# Pico_Audio_v0_13.net
KiCad netlist of a schematic drawn in EAGLE
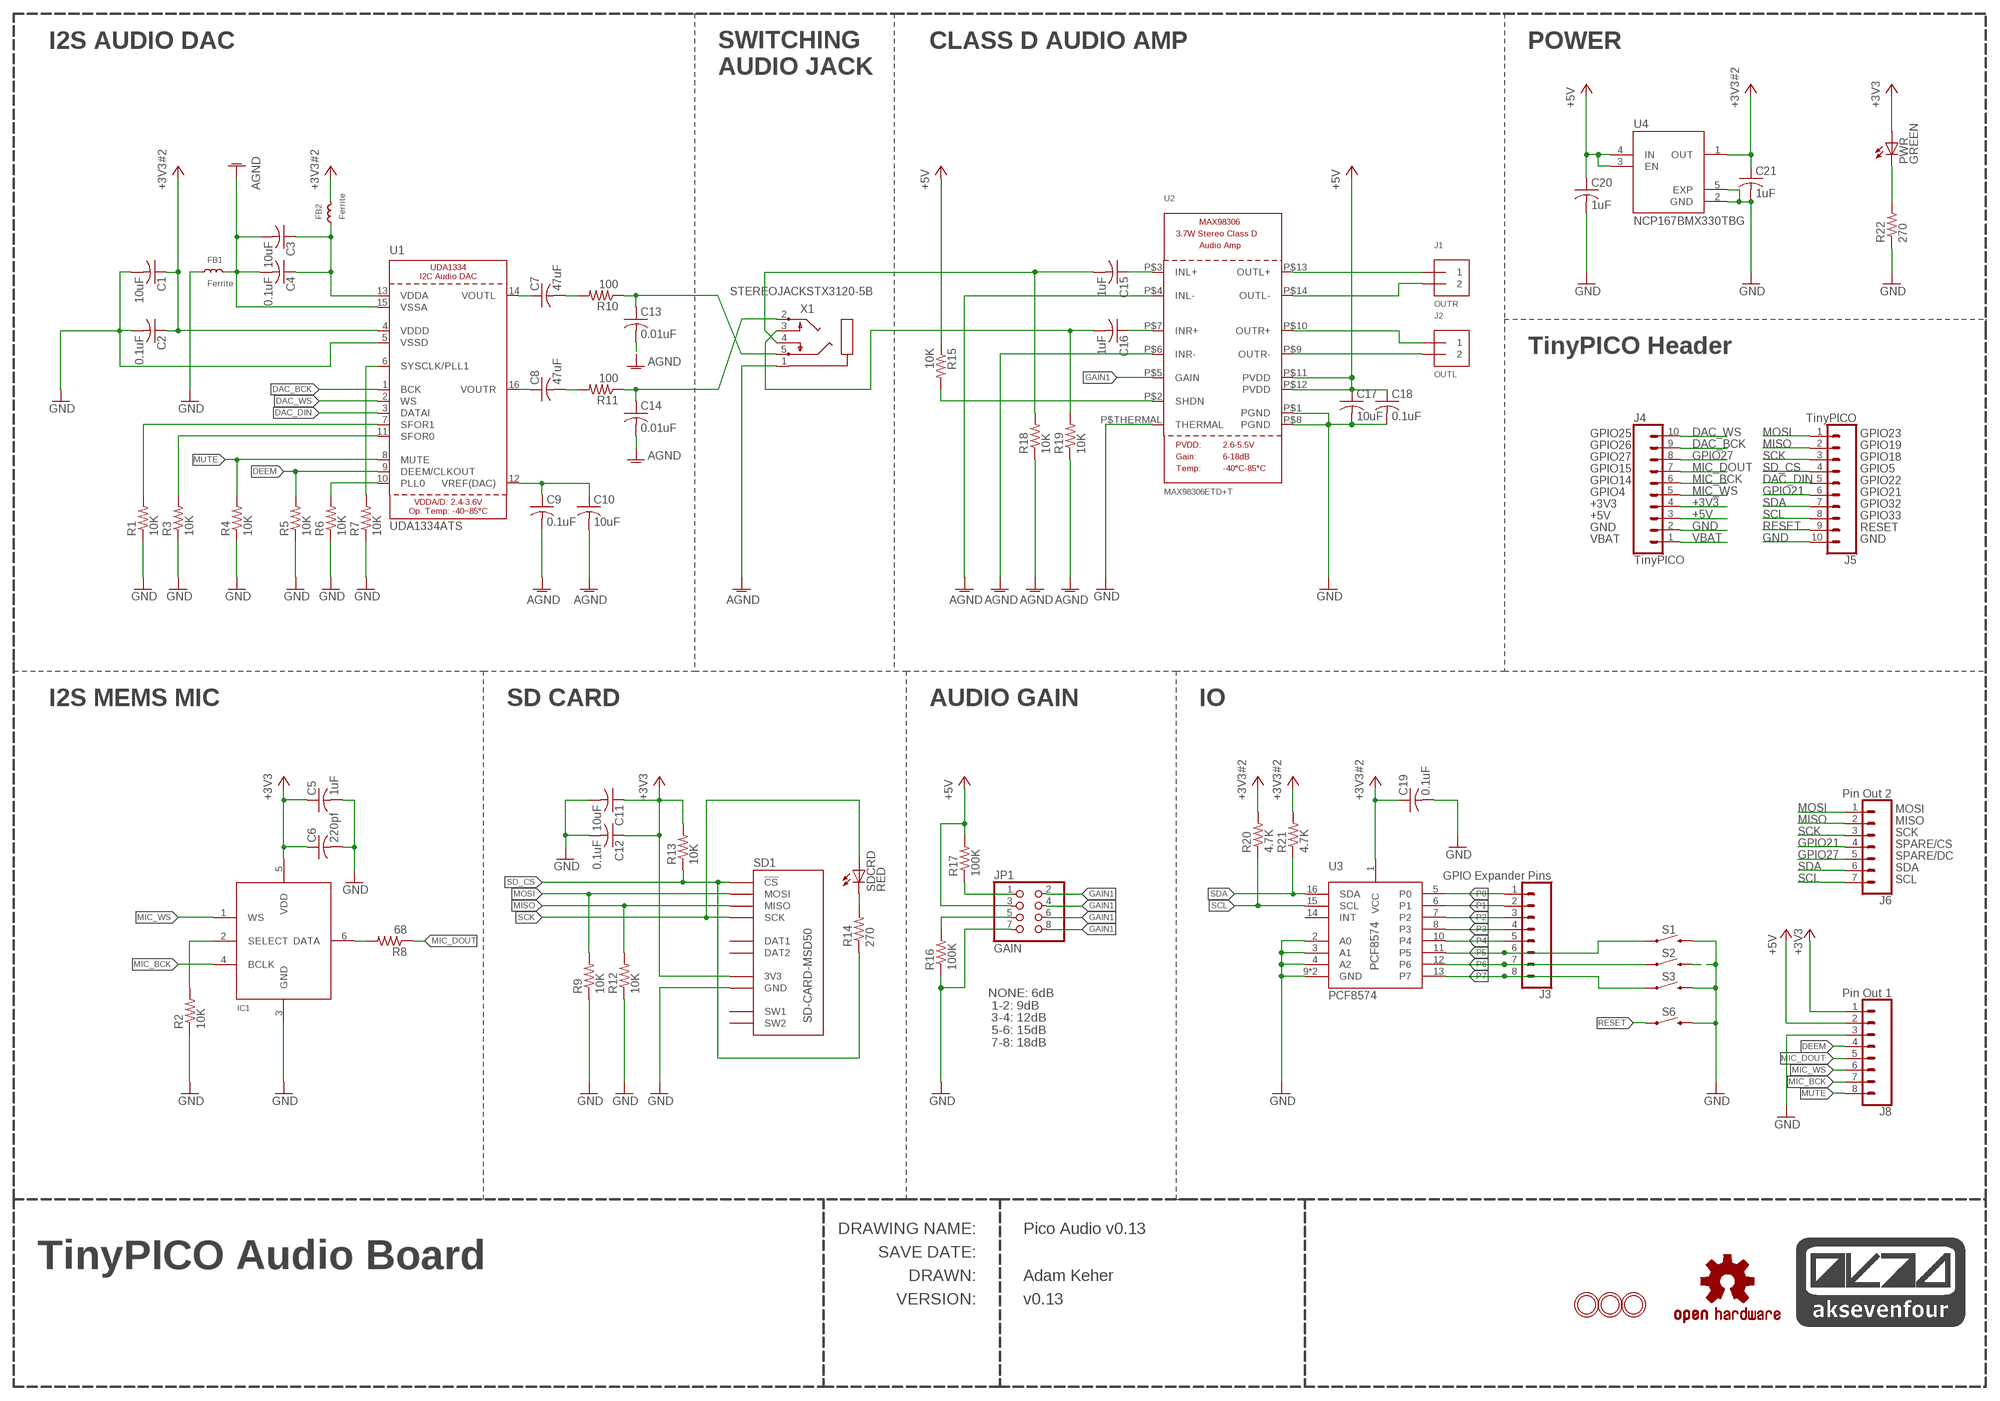
[diagram p0: schematic, sheet 1]

(export (version "E")
  (design (tool "Eeschema 10.0.6"))
  (components
    (comp (ref "AK74LOGO2")
      (value "AK74_LOGOAK74_LOGO_SMALL")
      (footprint "eagle-import:AK74_LOGO_MEDIUM")
      (libsource (lib "eagle-import") (part "AK74_LOGOAK74_LOGO_SMALL"))
    )
    (comp (ref "C1")
      (value "10uF")
      (footprint "eagle-import:C0603K")
      (libsource (lib "eagle-import") (part "C-USC0603K"))
    )
    (comp (ref "C2")
      (value "0.1uF")
      (footprint "eagle-import:C0402K")
      (libsource (lib "eagle-import") (part "C-USC0402K"))
    )
    (comp (ref "C3")
      (value "10uF")
      (footprint "eagle-import:C0603K")
      (libsource (lib "eagle-import") (part "C-USC0603K"))
    )
    (comp (ref "C4")
      (value "0.1uF")
      (footprint "eagle-import:C0402K")
      (libsource (lib "eagle-import") (part "C-USC0402K"))
    )
    (comp (ref "C5")
      (value "1uF")
      (footprint "eagle-import:C0402K")
      (libsource (lib "eagle-import") (part "C-USC0402K"))
    )
    (comp (ref "C6")
      (value "220pf")
      (footprint "eagle-import:C0402K")
      (libsource (lib "eagle-import") (part "C-USC0402K"))
    )
    (comp (ref "C7")
      (value "47uF")
      (footprint "eagle-import:C1210K")
      (libsource (lib "eagle-import") (part "C-USC1210K"))
    )
    (comp (ref "C8")
      (value "47uF")
      (footprint "eagle-import:C1210K")
      (libsource (lib "eagle-import") (part "C-USC1210K"))
    )
    (comp (ref "C9")
      (value "0.1uF")
      (footprint "eagle-import:C0402K")
      (libsource (lib "eagle-import") (part "C-USC0402K"))
    )
    (comp (ref "C10")
      (value "10uF")
      (footprint "eagle-import:C0603K")
      (libsource (lib "eagle-import") (part "C-USC0603K"))
    )
    (comp (ref "C11")
      (value "10uF")
      (footprint "eagle-import:C0603K")
      (libsource (lib "eagle-import") (part "C-USC0603K"))
    )
    (comp (ref "C12")
      (value "0.1uF")
      (footprint "eagle-import:C0402K")
      (libsource (lib "eagle-import") (part "C-USC0402K"))
    )
    (comp (ref "C13")
      (value "0.01uF")
      (footprint "eagle-import:C0402K")
      (libsource (lib "eagle-import") (part "C-USC0402K"))
    )
    (comp (ref "C14")
      (value "0.01uF")
      (footprint "eagle-import:C0402K")
      (libsource (lib "eagle-import") (part "C-USC0402K"))
    )
    (comp (ref "C15")
      (value "1uF")
      (footprint "eagle-import:C0402K")
      (libsource (lib "eagle-import") (part "C-USC0402K"))
    )
    (comp (ref "C16")
      (value "1uF")
      (footprint "eagle-import:C0402K")
      (libsource (lib "eagle-import") (part "C-USC0402K"))
    )
    (comp (ref "C17")
      (value "10uF")
      (footprint "eagle-import:C0603K")
      (libsource (lib "eagle-import") (part "C-USC0603K"))
    )
    (comp (ref "C18")
      (value "0.1uF")
      (footprint "eagle-import:C0402K")
      (libsource (lib "eagle-import") (part "C-USC0402K"))
    )
    (comp (ref "C19")
      (value "0.1uF")
      (footprint "eagle-import:C0402K")
      (libsource (lib "eagle-import") (part "C-USC0402K"))
    )
    (comp (ref "C20")
      (value "1uF")
      (footprint "eagle-import:C0402K")
      (libsource (lib "eagle-import") (part "C-USC0402K"))
    )
    (comp (ref "C21")
      (value "1uF")
      (footprint "eagle-import:C0402K")
      (libsource (lib "eagle-import") (part "C-USC0402K"))
    )
    (comp (ref "FB1")
      (value "Ferrite")
      (footprint "eagle-import:R0805")
      (libsource (lib "eagle-import") (part "FERRITEL0805"))
    )
    (comp (ref "FB2")
      (value "Ferrite")
      (footprint "eagle-import:R0805")
      (libsource (lib "eagle-import") (part "FERRITEL0805"))
    )
    (comp (ref "IC1")
      (value "MIC_I2S_SPH0645")
      (footprint "eagle-import:SPH0645LM4H")
      (libsource (lib "eagle-import") (part "MIC_I2S_SPH0645"))
    )
    (comp (ref "J1")
      (value "OUTR")
      (footprint "eagle-import:TERMBLOCK_1X2-3.5MM")
      (libsource (lib "eagle-import") (part "TERMBLOCK_1X2"))
    )
    (comp (ref "J2")
      (value "OUTL")
      (footprint "eagle-import:TERMBLOCK_1X2-3.5MM")
      (libsource (lib "eagle-import") (part "TERMBLOCK_1X2"))
    )
    (comp (ref "J3")
      (value "GPIO Expander Pins")
      (footprint "eagle-import:1X08_NO_SILK")
      (libsource (lib "eagle-import") (part "CONN_08NO_SILK_FEMALE_PTH"))
    )
    (comp (ref "J4")
      (value "TinyPICO")
      (footprint "eagle-import:1X10_NO_SILK")
      (libsource (lib "eagle-import") (part "TINYPICO_HEADER_10NO_SILK_PTH_FEMALE"))
    )
    (comp (ref "J5")
      (value "TinyPICO")
      (footprint "eagle-import:1X10_NO_SILK")
      (libsource (lib "eagle-import") (part "TINYPICO_HEADER_10NO_SILK_PTH_FEMALE"))
    )
    (comp (ref "J6")
      (value "Pin Out 2")
      (footprint "eagle-import:1X07_NO_SILK")
      (libsource (lib "eagle-import") (part "CONN_07NO_SILK"))
    )
    (comp (ref "J8")
      (value "Pin Out 1")
      (footprint "eagle-import:1X08_NO_SILK")
      (libsource (lib "eagle-import") (part "CONN_08NO_SILK_FEMALE_PTH"))
    )
    (comp (ref "JP1")
      (value "GAIN")
      (footprint "eagle-import:2X04")
      (libsource (lib "eagle-import") (part "PINHD-2X4"))
    )
    (comp (ref "LOGO1")
      (value "OSHW-LOGOM")
      (footprint "eagle-import:OSHW-LOGO-M")
      (libsource (lib "eagle-import") (part "OSHW-LOGOM"))
    )
    (comp (ref "MH1")
      (value "MOUNTINGHOLE2.5")
      (footprint "eagle-import:MOUNTINGHOLE_2.5_PLATED")
      (libsource (lib "eagle-import") (part "MOUNTINGHOLE2.5"))
    )
    (comp (ref "MH2")
      (value "MOUNTINGHOLE2.5")
      (footprint "eagle-import:MOUNTINGHOLE_2.5_PLATED")
      (libsource (lib "eagle-import") (part "MOUNTINGHOLE2.5"))
    )
    (comp (ref "MH3")
      (value "MOUNTINGHOLE2.5")
      (footprint "eagle-import:MOUNTINGHOLE_2.5_PLATED")
      (libsource (lib "eagle-import") (part "MOUNTINGHOLE2.5"))
    )
    (comp (ref "PWR")
      (value "GREEN")
      (footprint "eagle-import:CHIP-LED0805")
      (libsource (lib "eagle-import") (part "LEDCHIP-LED0805"))
    )
    (comp (ref "R1")
      (value "10K")
      (footprint "eagle-import:R0402")
      (libsource (lib "eagle-import") (part "R-US_R0402"))
    )
    (comp (ref "R2")
      (value "10K")
      (footprint "eagle-import:R0402")
      (libsource (lib "eagle-import") (part "R-US_R0402"))
    )
    (comp (ref "R3")
      (value "10K")
      (footprint "eagle-import:R0402")
      (libsource (lib "eagle-import") (part "R-US_R0402"))
    )
    (comp (ref "R4")
      (value "10K")
      (footprint "eagle-import:R0402")
      (libsource (lib "eagle-import") (part "R-US_R0402"))
    )
    (comp (ref "R5")
      (value "10K")
      (footprint "eagle-import:R0402")
      (libsource (lib "eagle-import") (part "R-US_R0402"))
    )
    (comp (ref "R6")
      (value "10K")
      (footprint "eagle-import:R0402")
      (libsource (lib "eagle-import") (part "R-US_R0402"))
    )
    (comp (ref "R7")
      (value "10K")
      (footprint "eagle-import:R0402")
      (libsource (lib "eagle-import") (part "R-US_R0402"))
    )
    (comp (ref "R8")
      (value "68")
      (footprint "eagle-import:R0402")
      (libsource (lib "eagle-import") (part "R-US_R0402"))
    )
    (comp (ref "R9")
      (value "10K")
      (footprint "eagle-import:R0402")
      (libsource (lib "eagle-import") (part "R-US_R0402"))
    )
    (comp (ref "R10")
      (value "100")
      (footprint "eagle-import:R0402")
      (libsource (lib "eagle-import") (part "R-US_R0402"))
    )
    (comp (ref "R11")
      (value "100")
      (footprint "eagle-import:R0402")
      (libsource (lib "eagle-import") (part "R-US_R0402"))
    )
    (comp (ref "R12")
      (value "10K")
      (footprint "eagle-import:R0402")
      (libsource (lib "eagle-import") (part "R-US_R0402"))
    )
    (comp (ref "R13")
      (value "10K")
      (footprint "eagle-import:R0402")
      (libsource (lib "eagle-import") (part "R-US_R0402"))
    )
    (comp (ref "R14")
      (value "270")
      (footprint "eagle-import:R0402")
      (libsource (lib "eagle-import") (part "R-US_R0402"))
    )
    (comp (ref "R15")
      (value "10K")
      (footprint "eagle-import:R0402")
      (libsource (lib "eagle-import") (part "R-US_R0402"))
    )
    (comp (ref "R16")
      (value "100K")
      (footprint "eagle-import:R0402")
      (libsource (lib "eagle-import") (part "R-US_R0402"))
    )
    (comp (ref "R17")
      (value "100K")
      (footprint "eagle-import:R0402")
      (libsource (lib "eagle-import") (part "R-US_R0402"))
    )
    (comp (ref "R18")
      (value "10K")
      (footprint "eagle-import:R0402")
      (libsource (lib "eagle-import") (part "R-US_R0402"))
    )
    (comp (ref "R19")
      (value "10K")
      (footprint "eagle-import:R0402")
      (libsource (lib "eagle-import") (part "R-US_R0402"))
    )
    (comp (ref "R20")
      (value "4.7K")
      (footprint "eagle-import:R0402")
      (libsource (lib "eagle-import") (part "R-US_R0402"))
    )
    (comp (ref "R21")
      (value "4.7K")
      (footprint "eagle-import:R0402")
      (libsource (lib "eagle-import") (part "R-US_R0402"))
    )
    (comp (ref "R22")
      (value "270")
      (footprint "eagle-import:R0402")
      (libsource (lib "eagle-import") (part "R-US_R0402"))
    )
    (comp (ref "S1")
      (value "MOMENTARY-SWITCH-SPST-SMD-4.6X2.8MM")
      (footprint "eagle-import:TACTILE_SWITCH_SMD_4.6X2.8MM")
      (libsource (lib "eagle-import") (part "MOMENTARY-SWITCH-SPST-SMD-4.6X2.8MM"))
    )
    (comp (ref "S2")
      (value "MOMENTARY-SWITCH-SPST-SMD-4.6X2.8MM")
      (footprint "eagle-import:TACTILE_SWITCH_SMD_4.6X2.8MM")
      (libsource (lib "eagle-import") (part "MOMENTARY-SWITCH-SPST-SMD-4.6X2.8MM"))
    )
    (comp (ref "S3")
      (value "MOMENTARY-SWITCH-SPST-SMD-4.6X2.8MM")
      (footprint "eagle-import:TACTILE_SWITCH_SMD_4.6X2.8MM")
      (libsource (lib "eagle-import") (part "MOMENTARY-SWITCH-SPST-SMD-4.6X2.8MM"))
    )
    (comp (ref "S6")
      (value "MOMENTARY-SWITCH-SPST-SMD-4.6X2.8MM")
      (footprint "eagle-import:TACTILE_SWITCH_SMD_4.6X2.8MM")
      (libsource (lib "eagle-import") (part "MOMENTARY-SWITCH-SPST-SMD-4.6X2.8MM"))
    )
    (comp (ref "SD1")
      (value "SD-CARD-MSD50")
      (footprint "eagle-import:SD_5031821853")
      (libsource (lib "eagle-import") (part "SD-CARD-MSD50"))
    )
    (comp (ref "SDCRD")
      (value "RED")
      (footprint "eagle-import:CHIP-LED0805")
      (libsource (lib "eagle-import") (part "LEDCHIP-LED0805"))
    )
    (comp (ref "U1")
      (value "UDA1334ATS")
      (footprint "eagle-import:SSOP16_4.4MM")
      (libsource (lib "eagle-import") (part "AUDIO_I2S_UDA1334{dblquote}{dblquote}"))
    )
    (comp (ref "U2")
      (value "MAX98306ETD+T")
      (footprint "eagle-import:TDFN14_3X3MM")
      (libsource (lib "eagle-import") (part "AUDIOAMP_MAX98306"))
    )
    (comp (ref "U3")
      (value "PCF8574")
      (footprint "eagle-import:QFN-16-3MM")
      (libsource (lib "eagle-import") (part "PCF8574"))
    )
    (comp (ref "U4")
      (value "NCP170AMX300TCG")
      (footprint "eagle-import:VREG_NCP170AMX300TCG")
      (fields (field (name "MF") "ON Semiconductor"))
      (libsource (lib "eagle-import") (part "NCP170AMX300TCG"))
    )
    (comp (ref "X1")
      (value "STEREOJACKSTX3120-5B")
      (footprint "eagle-import:STX3100")
      (libsource (lib "eagle-import") (part "STEREOJACKSTX3120-5B"))
    )
  )
  (nets
    (net (code "1") (name "+3V3") (class "Default")
      (node (ref "C11") (pin "1") (pinfunction "1_1") (pintype "passive"))
      (node (ref "C12") (pin "1") (pinfunction "1_1") (pintype "passive"))
      (node (ref "C5") (pin "1") (pinfunction "1_1") (pintype "passive"))
      (node (ref "C6") (pin "1") (pinfunction "1_1") (pintype "passive"))
      (node (ref "IC1") (pin "5") (pinfunction "VDD_5") (pintype "power_in"))
      (node (ref "J4") (pin "4") (pinfunction "4_4") (pintype "passive"))
      (node (ref "J8") (pin "1") (pinfunction "1_1") (pintype "passive"))
      (node (ref "PWR") (pin "A") (pinfunction "A_A") (pintype "passive"))
      (node (ref "R13") (pin "2") (pinfunction "2_2") (pintype "passive"))
      (node (ref "SD1") (pin "VCC") (pinfunction "3V3_VCC") (pintype "bidirectional"))
    )
    (net (code "2") (name "+3V3#2") (class "Default")
      (node (ref "C1") (pin "1") (pinfunction "1_1") (pintype "passive"))
      (node (ref "C19") (pin "1") (pinfunction "1_1") (pintype "passive"))
      (node (ref "C2") (pin "1") (pinfunction "1_1") (pintype "passive"))
      (node (ref "C21") (pin "1") (pinfunction "1_1") (pintype "passive"))
      (node (ref "FB2") (pin "2") (pinfunction "2_2") (pintype "passive"))
      (node (ref "R20") (pin "2") (pinfunction "2_2") (pintype "passive"))
      (node (ref "R21") (pin "2") (pinfunction "2_2") (pintype "passive"))
      (node (ref "U1") (pin "4") (pinfunction "VDDD_4") (pintype "power_in"))
      (node (ref "U3") (pin "1") (pinfunction "VCC_1") (pintype "bidirectional"))
      (node (ref "U4") (pin "1") (pinfunction "OUT_1") (pintype "output"))
    )
    (net (code "3") (name "+5V") (class "Default")
      (node (ref "C17") (pin "1") (pinfunction "1_1") (pintype "passive"))
      (node (ref "C18") (pin "1") (pinfunction "1_1") (pintype "passive"))
      (node (ref "C20") (pin "1") (pinfunction "1_1") (pintype "passive"))
      (node (ref "J4") (pin "3") (pinfunction "3_3") (pintype "passive"))
      (node (ref "J8") (pin "2") (pinfunction "2_2") (pintype "passive"))
      (node (ref "JP1") (pin "3") (pinfunction "3_3") (pintype "passive"))
      (node (ref "R15") (pin "1") (pinfunction "1_1") (pintype "passive"))
      (node (ref "R17") (pin "2") (pinfunction "2_2") (pintype "passive"))
      (node (ref "U2") (pin "P$11") (pinfunction "PVDD_P$11") (pintype "power_in"))
      (node (ref "U2") (pin "P$12") (pinfunction "PVDD_P$12") (pintype "power_in"))
      (node (ref "U4") (pin "3") (pinfunction "EN_3") (pintype "input"))
      (node (ref "U4") (pin "4") (pinfunction "IN_4") (pintype "input"))
    )
    (net (code "4") (name "/GPIO21") (class "Default")
      (node (ref "J5") (pin "6") (pinfunction "6_6") (pintype "passive"))
      (node (ref "J6") (pin "4") (pinfunction "4_4") (pintype "passive"))
    )
    (net (code "5") (name "/GPIO27") (class "Default")
      (node (ref "J4") (pin "8") (pinfunction "8_8") (pintype "passive"))
      (node (ref "J6") (pin "5") (pinfunction "5_5") (pintype "passive"))
    )
    (net (code "6") (name "/VBAT") (class "Default")
      (node (ref "J4") (pin "1") (pinfunction "1_1") (pintype "passive"))
    )
    (net (code "7") (name "AGND") (class "Default")
      (node (ref "C10") (pin "2") (pinfunction "2_2") (pintype "passive"))
      (node (ref "C13") (pin "2") (pinfunction "2_2") (pintype "passive"))
      (node (ref "C14") (pin "2") (pinfunction "2_2") (pintype "passive"))
      (node (ref "C3") (pin "2") (pinfunction "2_2") (pintype "passive"))
      (node (ref "C4") (pin "2") (pinfunction "2_2") (pintype "passive"))
      (node (ref "C9") (pin "2") (pinfunction "2_2") (pintype "passive"))
      (node (ref "FB1") (pin "2") (pinfunction "2_2") (pintype "passive"))
      (node (ref "R18") (pin "1") (pinfunction "1_1") (pintype "passive"))
      (node (ref "R19") (pin "1") (pinfunction "1_1") (pintype "passive"))
      (node (ref "U1") (pin "15") (pinfunction "VSSA_15") (pintype "power_in"))
      (node (ref "U2") (pin "P$4") (pinfunction "INL-_P$4") (pintype "input"))
      (node (ref "U2") (pin "P$6") (pinfunction "INR-_P$6") (pintype "input"))
      (node (ref "X1") (pin "1") (pinfunction "1_1") (pintype "passive"))
    )
    (net (code "8") (name "DAC_BCK") (class "Default")
      (node (ref "J4") (pin "9") (pinfunction "9_9") (pintype "passive"))
      (node (ref "U1") (pin "1") (pinfunction "BCK_1") (pintype "input"))
    )
    (net (code "9") (name "DAC_DIN") (class "Default")
      (node (ref "J5") (pin "5") (pinfunction "5_5") (pintype "passive"))
      (node (ref "U1") (pin "3") (pinfunction "DATAI_3") (pintype "input"))
    )
    (net (code "10") (name "DAC_WS") (class "Default")
      (node (ref "J4") (pin "10") (pinfunction "10_10") (pintype "passive"))
      (node (ref "U1") (pin "2") (pinfunction "WS_2") (pintype "input"))
    )
    (net (code "11") (name "DEEM") (class "Default")
      (node (ref "J8") (pin "4") (pinfunction "4_4") (pintype "passive"))
      (node (ref "R5") (pin "2") (pinfunction "2_2") (pintype "passive"))
      (node (ref "U1") (pin "9") (pinfunction "DEEM/CLKOUT_9") (pintype "bidirectional"))
    )
    (net (code "12") (name "GAIN1") (class "Default")
      (node (ref "JP1") (pin "2") (pinfunction "2_2") (pintype "passive"))
      (node (ref "JP1") (pin "4") (pinfunction "4_4") (pintype "passive"))
      (node (ref "JP1") (pin "6") (pinfunction "6_6") (pintype "passive"))
      (node (ref "JP1") (pin "8") (pinfunction "8_8") (pintype "passive"))
      (node (ref "U2") (pin "P$5") (pinfunction "GAIN_P$5") (pintype "input"))
    )
    (net (code "13") (name "GND") (class "Default")
      (node (ref "C1") (pin "2") (pinfunction "2_2") (pintype "passive"))
      (node (ref "C11") (pin "2") (pinfunction "2_2") (pintype "passive"))
      (node (ref "C12") (pin "2") (pinfunction "2_2") (pintype "passive"))
      (node (ref "C17") (pin "2") (pinfunction "2_2") (pintype "passive"))
      (node (ref "C18") (pin "2") (pinfunction "2_2") (pintype "passive"))
      (node (ref "C19") (pin "2") (pinfunction "2_2") (pintype "passive"))
      (node (ref "C2") (pin "2") (pinfunction "2_2") (pintype "passive"))
      (node (ref "C20") (pin "2") (pinfunction "2_2") (pintype "passive"))
      (node (ref "C21") (pin "2") (pinfunction "2_2") (pintype "passive"))
      (node (ref "C5") (pin "2") (pinfunction "2_2") (pintype "passive"))
      (node (ref "C6") (pin "2") (pinfunction "2_2") (pintype "passive"))
      (node (ref "FB1") (pin "1") (pinfunction "1_1") (pintype "passive"))
      (node (ref "IC1") (pin "3") (pinfunction "GND_3") (pintype "power_in"))
      (node (ref "J4") (pin "2") (pinfunction "2_2") (pintype "passive"))
      (node (ref "J5") (pin "10") (pinfunction "10_10") (pintype "passive"))
      (node (ref "J8") (pin "3") (pinfunction "3_3") (pintype "passive"))
      (node (ref "JP1") (pin "7") (pinfunction "7_7") (pintype "passive"))
      (node (ref "R1") (pin "1") (pinfunction "1_1") (pintype "passive"))
      (node (ref "R12") (pin "1") (pinfunction "1_1") (pintype "passive"))
      (node (ref "R16") (pin "1") (pinfunction "1_1") (pintype "passive"))
      (node (ref "R2") (pin "1") (pinfunction "1_1") (pintype "passive"))
      (node (ref "R22") (pin "1") (pinfunction "1_1") (pintype "passive"))
      (node (ref "R3") (pin "1") (pinfunction "1_1") (pintype "passive"))
      (node (ref "R4") (pin "1") (pinfunction "1_1") (pintype "passive"))
      (node (ref "R5") (pin "1") (pinfunction "1_1") (pintype "passive"))
      (node (ref "R6") (pin "1") (pinfunction "1_1") (pintype "passive"))
      (node (ref "R7") (pin "1") (pinfunction "1_1") (pintype "passive"))
      (node (ref "R9") (pin "1") (pinfunction "1_1") (pintype "passive"))
      (node (ref "S1") (pin "3") (pinfunction "2_3") (pintype "passive"))
      (node (ref "S1") (pin "4") (pinfunction "2_4") (pintype "passive"))
      (node (ref "S2") (pin "3") (pinfunction "2_3") (pintype "passive"))
      (node (ref "S2") (pin "4") (pinfunction "2_4") (pintype "passive"))
      (node (ref "S3") (pin "3") (pinfunction "2_3") (pintype "passive"))
      (node (ref "S3") (pin "4") (pinfunction "2_4") (pintype "passive"))
      (node (ref "S6") (pin "3") (pinfunction "2_3") (pintype "passive"))
      (node (ref "S6") (pin "4") (pinfunction "2_4") (pintype "passive"))
      (node (ref "SD1") (pin "GND") (pinfunction "GND_GND") (pintype "bidirectional"))
      (node (ref "U1") (pin "5") (pinfunction "VSSD_5") (pintype "power_in"))
      (node (ref "U2") (pin "P$1") (pinfunction "PGND_P$1") (pintype "power_in"))
      (node (ref "U2") (pin "P$8") (pinfunction "PGND_P$8") (pintype "power_in"))
      (node (ref "U2") (pin "P$THERMAL") (pinfunction "THERMAL_P$THERMAL") (pintype "power_in"))
      (node (ref "U3") (pin "2") (pinfunction "A0_2") (pintype "bidirectional"))
      (node (ref "U3") (pin "3") (pinfunction "A1_3") (pintype "bidirectional"))
      (node (ref "U3") (pin "4") (pinfunction "A2_4") (pintype "bidirectional"))
      (node (ref "U3") (pin "9") (pinfunction "GND_9") (pintype "bidirectional"))
      (node (ref "U3") (pin "P$1") (pinfunction "GND_P$1") (pintype "bidirectional"))
      (node (ref "U4") (pin "2") (pinfunction "GND_2") (pintype "power_in"))
      (node (ref "U4") (pin "5") (pinfunction "EXP_5") (pintype "power_in"))
    )
    (net (code "14") (name "MIC_BCK") (class "Default")
      (node (ref "IC1") (pin "4") (pinfunction "BCLK_4") (pintype "input"))
      (node (ref "J4") (pin "6") (pinfunction "6_6") (pintype "passive"))
      (node (ref "J8") (pin "7") (pinfunction "7_7") (pintype "passive"))
    )
    (net (code "15") (name "MIC_DOUT") (class "Default")
      (node (ref "J4") (pin "7") (pinfunction "7_7") (pintype "passive"))
      (node (ref "J8") (pin "5") (pinfunction "5_5") (pintype "passive"))
      (node (ref "R8") (pin "1") (pinfunction "1_1") (pintype "passive"))
    )
    (net (code "16") (name "MIC_WS") (class "Default")
      (node (ref "IC1") (pin "1") (pinfunction "WS_1") (pintype "input"))
      (node (ref "J4") (pin "5") (pinfunction "5_5") (pintype "passive"))
      (node (ref "J8") (pin "6") (pinfunction "6_6") (pintype "passive"))
    )
    (net (code "17") (name "MISO") (class "Default")
      (node (ref "J5") (pin "2") (pinfunction "2_2") (pintype "passive"))
      (node (ref "J6") (pin "2") (pinfunction "2_2") (pintype "passive"))
      (node (ref "R12") (pin "2") (pinfunction "2_2") (pintype "passive"))
      (node (ref "SD1") (pin "MISO") (pinfunction "MISO_MISO") (pintype "bidirectional"))
    )
    (net (code "18") (name "MOSI") (class "Default")
      (node (ref "J5") (pin "1") (pinfunction "1_1") (pintype "passive"))
      (node (ref "J6") (pin "1") (pinfunction "1_1") (pintype "passive"))
      (node (ref "R9") (pin "2") (pinfunction "2_2") (pintype "passive"))
      (node (ref "SD1") (pin "MOSI") (pinfunction "MOSI_MOSI") (pintype "bidirectional"))
    )
    (net (code "19") (name "MUTE") (class "Default")
      (node (ref "J8") (pin "8") (pinfunction "8_8") (pintype "passive"))
      (node (ref "R4") (pin "2") (pinfunction "2_2") (pintype "passive"))
      (node (ref "U1") (pin "8") (pinfunction "MUTE_8") (pintype "input"))
    )
    (net (code "20") (name "Net-(C7-Pad2)") (class "Default")
      (node (ref "C7") (pin "2") (pinfunction "2_2") (pintype "passive"))
      (node (ref "R10") (pin "2") (pinfunction "2_2") (pintype "passive"))
    )
    (net (code "21") (name "Net-(C8-Pad2)") (class "Default")
      (node (ref "C8") (pin "2") (pinfunction "2_2") (pintype "passive"))
      (node (ref "R11") (pin "2") (pinfunction "2_2") (pintype "passive"))
    )
    (net (code "22") (name "Net-(C13-Pad1)") (class "Default")
      (node (ref "C13") (pin "1") (pinfunction "1_1") (pintype "passive"))
      (node (ref "R10") (pin "1") (pinfunction "1_1") (pintype "passive"))
      (node (ref "X1") (pin "5") (pinfunction "5_5") (pintype "passive"))
    )
    (net (code "23") (name "Net-(C14-Pad1)") (class "Default")
      (node (ref "C14") (pin "1") (pinfunction "1_1") (pintype "passive"))
      (node (ref "R11") (pin "1") (pinfunction "1_1") (pintype "passive"))
      (node (ref "X1") (pin "2") (pinfunction "2_2") (pintype "passive"))
    )
    (net (code "24") (name "Net-(C15-Pad2)") (class "Default")
      (node (ref "C15") (pin "2") (pinfunction "2_2") (pintype "passive"))
      (node (ref "R18") (pin "2") (pinfunction "2_2") (pintype "passive"))
      (node (ref "X1") (pin "4") (pinfunction "4_4") (pintype "passive"))
    )
    (net (code "25") (name "Net-(C16-Pad2)") (class "Default")
      (node (ref "C16") (pin "2") (pinfunction "2_2") (pintype "passive"))
      (node (ref "R19") (pin "2") (pinfunction "2_2") (pintype "passive"))
      (node (ref "X1") (pin "3") (pinfunction "3_3") (pintype "passive"))
    )
    (net (code "26") (name "Net-(IC1-DATA)") (class "Default")
      (node (ref "IC1") (pin "6") (pinfunction "DATA_6") (pintype "output"))
      (node (ref "R8") (pin "2") (pinfunction "2_2") (pintype "passive"))
    )
    (net (code "27") (name "Net-(IC1-SELECT)") (class "Default")
      (node (ref "IC1") (pin "2") (pinfunction "SELECT_2") (pintype "input"))
      (node (ref "R2") (pin "2") (pinfunction "2_2") (pintype "passive"))
    )
    (net (code "28") (name "Net-(JP1-Pad1)") (class "Default")
      (node (ref "JP1") (pin "1") (pinfunction "1_1") (pintype "passive"))
      (node (ref "R17") (pin "1") (pinfunction "1_1") (pintype "passive"))
    )
    (net (code "29") (name "Net-(JP1-Pad5)") (class "Default")
      (node (ref "JP1") (pin "5") (pinfunction "5_5") (pintype "passive"))
      (node (ref "R16") (pin "2") (pinfunction "2_2") (pintype "passive"))
    )
    (net (code "30") (name "Net-(PWR-PadC)") (class "Default")
      (node (ref "PWR") (pin "C") (pinfunction "C_C") (pintype "passive"))
      (node (ref "R22") (pin "2") (pinfunction "2_2") (pintype "passive"))
    )
    (net (code "31") (name "Net-(R14-Pad2)") (class "Default")
      (node (ref "R14") (pin "2") (pinfunction "2_2") (pintype "passive"))
      (node (ref "SDCRD") (pin "C") (pinfunction "C_C") (pintype "passive"))
    )
    (net (code "32") (name "Net-(U1-PLL0)") (class "Default")
      (node (ref "R6") (pin "2") (pinfunction "2_2") (pintype "passive"))
      (node (ref "U1") (pin "10") (pinfunction "PLL0_10") (pintype "input"))
    )
    (net (code "33") (name "Net-(U1-SFOR0)") (class "Default")
      (node (ref "R3") (pin "2") (pinfunction "2_2") (pintype "passive"))
      (node (ref "U1") (pin "11") (pinfunction "SFOR0_11") (pintype "input"))
    )
    (net (code "34") (name "Net-(U1-SFOR1)") (class "Default")
      (node (ref "R1") (pin "2") (pinfunction "2_2") (pintype "passive"))
      (node (ref "U1") (pin "7") (pinfunction "SFOR1_7") (pintype "input"))
    )
    (net (code "35") (name "Net-(U1-SYSCLK{slash}PLL1)") (class "Default")
      (node (ref "R7") (pin "2") (pinfunction "2_2") (pintype "passive"))
      (node (ref "U1") (pin "6") (pinfunction "SYSCLK/PLL1_6") (pintype "input"))
    )
    (net (code "36") (name "Net-(U1-VDDA)") (class "Default")
      (node (ref "C3") (pin "1") (pinfunction "1_1") (pintype "passive"))
      (node (ref "C4") (pin "1") (pinfunction "1_1") (pintype "passive"))
      (node (ref "FB2") (pin "1") (pinfunction "1_1") (pintype "passive"))
      (node (ref "U1") (pin "13") (pinfunction "VDDA_13") (pintype "power_in"))
    )
    (net (code "37") (name "Net-(U1-VOUTL)") (class "Default")
      (node (ref "C7") (pin "1") (pinfunction "1_1") (pintype "passive"))
      (node (ref "U1") (pin "14") (pinfunction "VOUTL_14") (pintype "output"))
    )
    (net (code "38") (name "Net-(U1-VOUTR)") (class "Default")
      (node (ref "C8") (pin "1") (pinfunction "1_1") (pintype "passive"))
      (node (ref "U1") (pin "16") (pinfunction "VOUTR_16") (pintype "output"))
    )
    (net (code "39") (name "Net-(U1-VREF(DAC))") (class "Default")
      (node (ref "C10") (pin "1") (pinfunction "1_1") (pintype "passive"))
      (node (ref "C9") (pin "1") (pinfunction "1_1") (pintype "passive"))
      (node (ref "U1") (pin "12") (pinfunction "VREF(DAC)_12") (pintype "output"))
    )
    (net (code "40") (name "Net-(U2-INL+)") (class "Default")
      (node (ref "C15") (pin "1") (pinfunction "1_1") (pintype "passive"))
      (node (ref "U2") (pin "P$3") (pinfunction "INL+_P$3") (pintype "input"))
    )
    (net (code "41") (name "Net-(U2-INR+)") (class "Default")
      (node (ref "C16") (pin "1") (pinfunction "1_1") (pintype "passive"))
      (node (ref "U2") (pin "P$7") (pinfunction "INR+_P$7") (pintype "input"))
    )
    (net (code "42") (name "Net-(U2-OUTL+)") (class "Default")
      (node (ref "J1") (pin "1") (pinfunction "1_1") (pintype "passive"))
      (node (ref "U2") (pin "P$13") (pinfunction "OUTL+_P$13") (pintype "output"))
    )
    (net (code "43") (name "Net-(U2-OUTL-)") (class "Default")
      (node (ref "J1") (pin "2") (pinfunction "2_2") (pintype "passive"))
      (node (ref "U2") (pin "P$14") (pinfunction "OUTL-_P$14") (pintype "output"))
    )
    (net (code "44") (name "Net-(U2-OUTR+)") (class "Default")
      (node (ref "J2") (pin "1") (pinfunction "1_1") (pintype "passive"))
      (node (ref "U2") (pin "P$10") (pinfunction "OUTR+_P$10") (pintype "output"))
    )
    (net (code "45") (name "Net-(U2-OUTR-)") (class "Default")
      (node (ref "J2") (pin "2") (pinfunction "2_2") (pintype "passive"))
      (node (ref "U2") (pin "P$9") (pinfunction "OUTR-_P$9") (pintype "output"))
    )
    (net (code "46") (name "Net-(U2-SHDN)") (class "Default")
      (node (ref "R15") (pin "2") (pinfunction "2_2") (pintype "passive"))
      (node (ref "U2") (pin "P$2") (pinfunction "SHDN_P$2") (pintype "input"))
    )
    (net (code "47") (name "P0") (class "Default")
      (node (ref "J3") (pin "1") (pinfunction "1_1") (pintype "passive"))
      (node (ref "U3") (pin "5") (pinfunction "P0_5") (pintype "bidirectional"))
    )
    (net (code "48") (name "P1") (class "Default")
      (node (ref "J3") (pin "2") (pinfunction "2_2") (pintype "passive"))
      (node (ref "U3") (pin "6") (pinfunction "P1_6") (pintype "bidirectional"))
    )
    (net (code "49") (name "P2") (class "Default")
      (node (ref "J3") (pin "3") (pinfunction "3_3") (pintype "passive"))
      (node (ref "U3") (pin "7") (pinfunction "P2_7") (pintype "bidirectional"))
    )
    (net (code "50") (name "P3") (class "Default")
      (node (ref "J3") (pin "4") (pinfunction "4_4") (pintype "passive"))
      (node (ref "U3") (pin "8") (pinfunction "P3_8") (pintype "bidirectional"))
    )
    (net (code "51") (name "P4") (class "Default")
      (node (ref "J3") (pin "5") (pinfunction "5_5") (pintype "passive"))
      (node (ref "U3") (pin "10") (pinfunction "P4_10") (pintype "bidirectional"))
    )
    (net (code "52") (name "P5") (class "Default")
      (node (ref "J3") (pin "6") (pinfunction "6_6") (pintype "passive"))
      (node (ref "S1") (pin "1") (pinfunction "1_1") (pintype "passive"))
      (node (ref "S1") (pin "2") (pinfunction "1_2") (pintype "passive"))
      (node (ref "U3") (pin "11") (pinfunction "P5_11") (pintype "bidirectional"))
    )
    (net (code "53") (name "P6") (class "Default")
      (node (ref "J3") (pin "7") (pinfunction "7_7") (pintype "passive"))
      (node (ref "S2") (pin "1") (pinfunction "1_1") (pintype "passive"))
      (node (ref "S2") (pin "2") (pinfunction "1_2") (pintype "passive"))
      (node (ref "U3") (pin "12") (pinfunction "P6_12") (pintype "bidirectional"))
    )
    (net (code "54") (name "P7") (class "Default")
      (node (ref "J3") (pin "8") (pinfunction "8_8") (pintype "passive"))
      (node (ref "S3") (pin "1") (pinfunction "1_1") (pintype "passive"))
      (node (ref "S3") (pin "2") (pinfunction "1_2") (pintype "passive"))
      (node (ref "U3") (pin "13") (pinfunction "P7_13") (pintype "bidirectional"))
    )
    (net (code "55") (name "RESET") (class "Default")
      (node (ref "J5") (pin "9") (pinfunction "9_9") (pintype "passive"))
      (node (ref "S6") (pin "1") (pinfunction "1_1") (pintype "passive"))
      (node (ref "S6") (pin "2") (pinfunction "1_2") (pintype "passive"))
    )
    (net (code "56") (name "SCK") (class "Default")
      (node (ref "J5") (pin "3") (pinfunction "3_3") (pintype "passive"))
      (node (ref "J6") (pin "3") (pinfunction "3_3") (pintype "passive"))
      (node (ref "SD1") (pin "SCK") (pinfunction "SCK_SCK") (pintype "bidirectional"))
      (node (ref "SDCRD") (pin "A") (pinfunction "A_A") (pintype "passive"))
    )
    (net (code "57") (name "SCL") (class "Default")
      (node (ref "J5") (pin "8") (pinfunction "8_8") (pintype "passive"))
      (node (ref "J6") (pin "7") (pinfunction "7_7") (pintype "passive"))
      (node (ref "R20") (pin "1") (pinfunction "1_1") (pintype "passive"))
      (node (ref "U3") (pin "15") (pinfunction "SCL_15") (pintype "bidirectional"))
    )
    (net (code "58") (name "SDA") (class "Default")
      (node (ref "J5") (pin "7") (pinfunction "7_7") (pintype "passive"))
      (node (ref "J6") (pin "6") (pinfunction "6_6") (pintype "passive"))
      (node (ref "R21") (pin "1") (pinfunction "1_1") (pintype "passive"))
      (node (ref "U3") (pin "16") (pinfunction "SDA_16") (pintype "bidirectional"))
    )
    (net (code "59") (name "SD_CS") (class "Default")
      (node (ref "J5") (pin "4") (pinfunction "4_4") (pintype "passive"))
      (node (ref "R13") (pin "1") (pinfunction "1_1") (pintype "passive"))
      (node (ref "R14") (pin "1") (pinfunction "1_1") (pintype "passive"))
      (node (ref "SD1") (pin "CS") (pinfunction "~{CS}_CS") (pintype "bidirectional"))
    )
    (net (code "60") (name "unconnected-(SD1-PadDAT1)") (class "Default")
      (node (ref "SD1") (pin "DAT1") (pinfunction "DAT1_DAT1") (pintype "bidirectional"))
    )
    (net (code "61") (name "unconnected-(SD1-PadDAT2)") (class "Default")
      (node (ref "SD1") (pin "DAT2") (pinfunction "DAT2_DAT2") (pintype "bidirectional"))
    )
    (net (code "62") (name "unconnected-(SD1-PadSW1)") (class "Default")
      (node (ref "SD1") (pin "SW1") (pinfunction "SW1_SW1") (pintype "bidirectional"))
    )
    (net (code "63") (name "unconnected-(SD1-PadSW2)") (class "Default")
      (node (ref "SD1") (pin "SW2") (pinfunction "SW2_SW2") (pintype "bidirectional"))
    )
    (net (code "64") (name "unconnected-(U3-INT-Pad14)") (class "Default")
      (node (ref "U3") (pin "14") (pinfunction "INT_14") (pintype "bidirectional"))
    )
  )
)
